# USB_Serial.net
KiCad netlist of a schematic drawn in Altium Designer
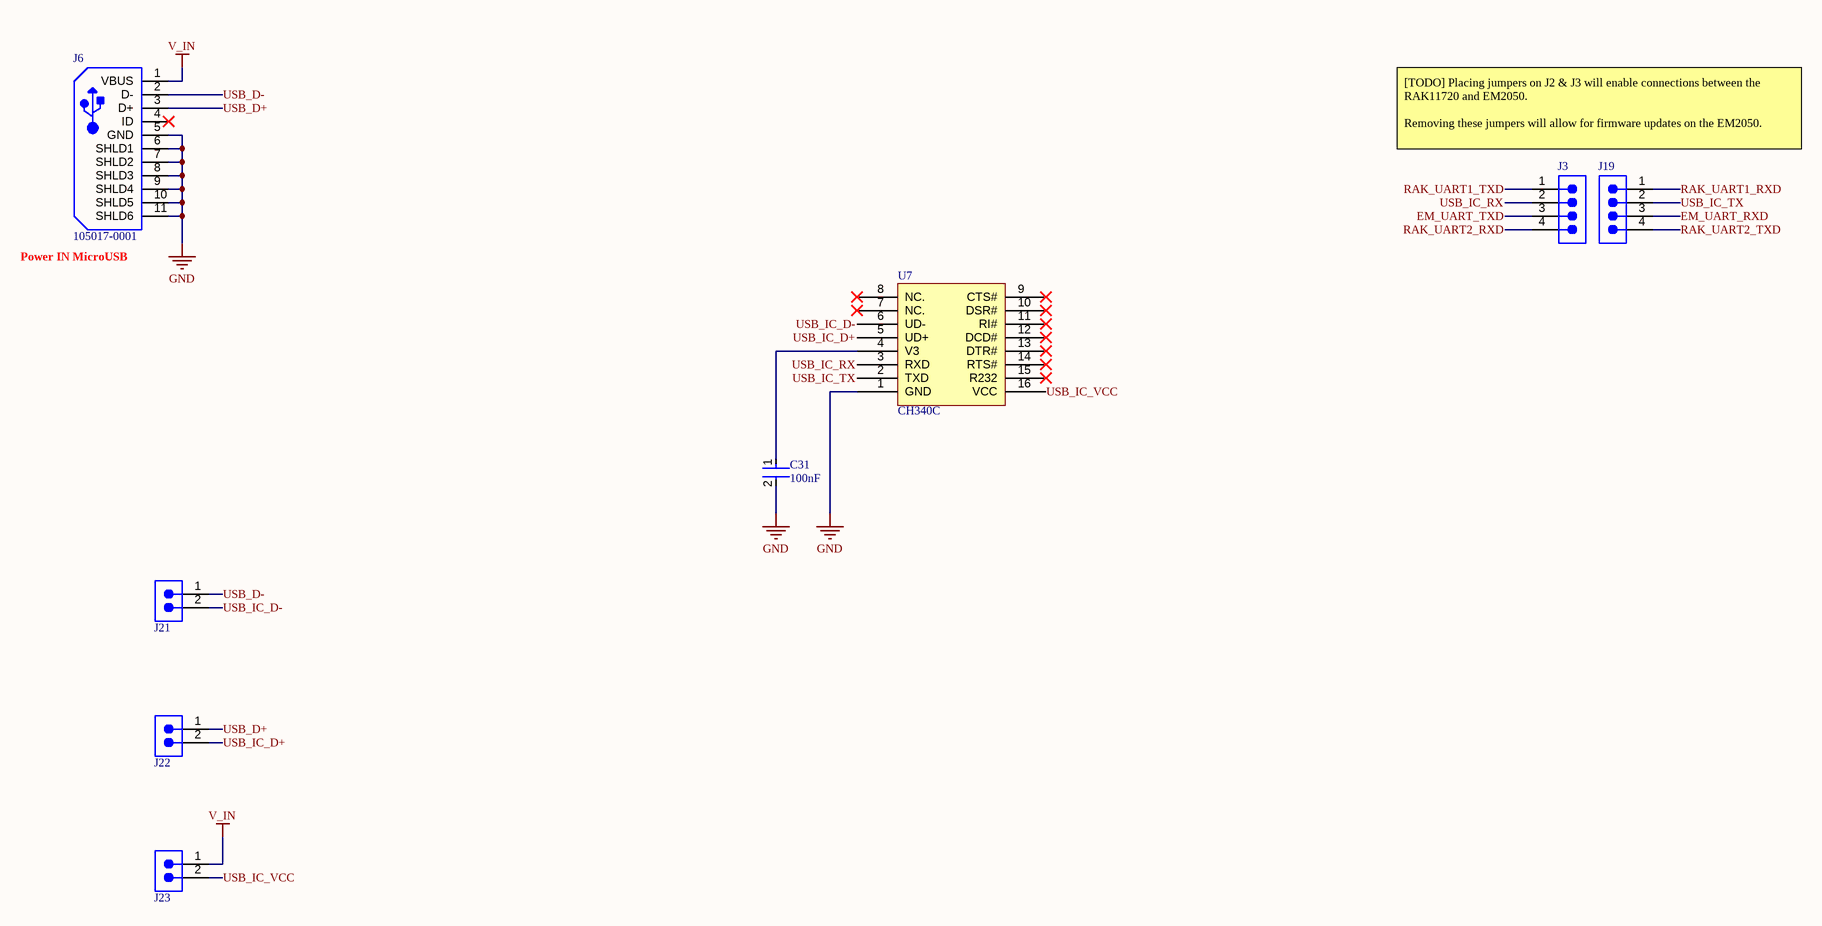
[diagram p0: USB_Serial.SchDoc]

(export (version "E")
  (design (tool "Eeschema 10.0.6"))
  (components
    (comp (ref "C31")
      (value "0402ZD104KAT2A")
      (footprint "FP-0402-L_1_0_1-W_0_5_0_1-IPC_C")
      (description "General Purpose Ceramic Capacitor, 0402, 100nF, 10%, X5R, 15%, 10V")
      (fields
        (field (name "VOLTAGE") "10V")
        (field (name "TOLERANCE") "10%")
        (field (name "CAPACITANCE") "100nF")
      )
      (libsource (lib "ApolloEcho_Dev_Kit") (part "b4654b650e69147ec39a6b967a45e02"))
    )
    (comp (ref "J3")
      (value "61300411121")
      (footprint "61300411121")
      (libsource (lib "ApolloEcho_Dev_Kit") (part "Header_Male_1R_04P"))
    )
    (comp (ref "J6")
      (value "105017-0001")
      (footprint "USB-MICRO-B_V")
      (fields (field (name "MANUFACTURER") "Molex"))
      (libsource (lib "ApolloEcho_Dev_Kit") (part "USB-5-6SHLD"))
    )
    (comp (ref "J19")
      (value "61300411121")
      (footprint "61300411121")
      (libsource (lib "ApolloEcho_Dev_Kit") (part "Header_Male_1R_04P"))
    )
    (comp (ref "J21")
      (value "61300211121")
      (footprint "61300211121")
      (libsource (lib "ApolloEcho_Dev_Kit") (part "Header_Male_1R_02P"))
    )
    (comp (ref "J22")
      (value "61300211121")
      (footprint "61300211121")
      (libsource (lib "ApolloEcho_Dev_Kit") (part "Header_Male_1R_02P"))
    )
    (comp (ref "J23")
      (value "61300211121")
      (footprint "61300211121")
      (libsource (lib "ApolloEcho_Dev_Kit") (part "Header_Male_1R_02P"))
    )
    (comp (ref "U7")
      (value "CH340C")
      (footprint "CH340C")
      (description "USB to Serial CH340 IC")
      (libsource (lib "ApolloEcho_Dev_Kit") (part "CH340C"))
    )
  )
  (nets
    (net (code "1") (name "/EM_UART_RXD") (class "Default")
      (node (ref "J19") (pin "3") (pinfunction "3_3") (pintype "passive"))
    )
    (net (code "2") (name "/EM_UART_TXD") (class "Default")
      (node (ref "J3") (pin "3") (pinfunction "3_3") (pintype "passive"))
    )
    (net (code "3") (name "/RAK_UART1_RXD") (class "Default")
      (node (ref "J19") (pin "1") (pinfunction "1_1") (pintype "passive"))
    )
    (net (code "4") (name "/RAK_UART1_TXD") (class "Default")
      (node (ref "J3") (pin "1") (pinfunction "1_1") (pintype "passive"))
    )
    (net (code "5") (name "/RAK_UART2_RXD") (class "Default")
      (node (ref "J3") (pin "4") (pinfunction "4_4") (pintype "passive"))
    )
    (net (code "6") (name "/RAK_UART2_TXD") (class "Default")
      (node (ref "J19") (pin "4") (pinfunction "4_4") (pintype "passive"))
    )
    (net (code "7") (name "/USB_D+") (class "Default")
      (node (ref "J22") (pin "1") (pinfunction "1_1") (pintype "passive"))
      (node (ref "J6") (pin "3") (pinfunction "D+_3") (pintype "passive"))
    )
    (net (code "8") (name "/USB_D-") (class "Default")
      (node (ref "J21") (pin "1") (pinfunction "1_1") (pintype "passive"))
      (node (ref "J6") (pin "2") (pinfunction "D-_2") (pintype "passive"))
    )
    (net (code "9") (name "/USB_IC_D+") (class "Default")
      (node (ref "J22") (pin "2") (pinfunction "2_2") (pintype "passive"))
      (node (ref "U7") (pin "5") (pinfunction "UD+_5") (pintype "passive"))
    )
    (net (code "10") (name "/USB_IC_D-") (class "Default")
      (node (ref "J21") (pin "2") (pinfunction "2_2") (pintype "passive"))
      (node (ref "U7") (pin "6") (pinfunction "UD-_6") (pintype "passive"))
    )
    (net (code "11") (name "/USB_IC_RX") (class "Default")
      (node (ref "J3") (pin "2") (pinfunction "2_2") (pintype "passive"))
      (node (ref "U7") (pin "3") (pinfunction "RXD_3") (pintype "passive"))
    )
    (net (code "12") (name "/USB_IC_TX") (class "Default")
      (node (ref "J19") (pin "2") (pinfunction "2_2") (pintype "passive"))
      (node (ref "U7") (pin "2") (pinfunction "TXD_2") (pintype "passive"))
    )
    (net (code "13") (name "/USB_IC_VCC") (class "Default")
      (node (ref "J23") (pin "2") (pinfunction "2_2") (pintype "passive"))
      (node (ref "U7") (pin "16") (pinfunction "VCC_16") (pintype "passive"))
    )
    (net (code "14") (name "GND") (class "Default")
      (node (ref "C31") (pin "2") (pinfunction "2_2") (pintype "passive"))
      (node (ref "J6") (pin "10") (pinfunction "SHLD5_10") (pintype "passive"))
      (node (ref "J6") (pin "11") (pinfunction "SHLD6_11") (pintype "passive"))
      (node (ref "J6") (pin "5") (pinfunction "GND_5") (pintype "passive"))
      (node (ref "J6") (pin "6") (pinfunction "SHLD1_6") (pintype "passive"))
      (node (ref "J6") (pin "7") (pinfunction "SHLD2_7") (pintype "passive"))
      (node (ref "J6") (pin "8") (pinfunction "SHLD3_8") (pintype "passive"))
      (node (ref "J6") (pin "9") (pinfunction "SHLD4_9") (pintype "passive"))
      (node (ref "U7") (pin "1") (pinfunction "GND_1") (pintype "passive"))
    )
    (net (code "15") (name "Net-(U7-V3)") (class "Default")
      (node (ref "C31") (pin "1") (pinfunction "1_1") (pintype "passive"))
      (node (ref "U7") (pin "4") (pinfunction "V3_4") (pintype "passive"))
    )
    (net (code "16") (name "V_IN") (class "Default")
      (node (ref "J23") (pin "1") (pinfunction "1_1") (pintype "passive"))
      (node (ref "J6") (pin "1") (pinfunction "VBUS_1") (pintype "passive"))
    )
    (net (code "17") (name "unconnected-(J6-ID-Pad4)") (class "Default")
      (node (ref "J6") (pin "4") (pinfunction "ID_4") (pintype "passive+no_connect"))
    )
    (net (code "18") (name "unconnected-(U7-CTS#-Pad9)") (class "Default")
      (node (ref "U7") (pin "9") (pinfunction "CTS#_9") (pintype "passive+no_connect"))
    )
    (net (code "19") (name "unconnected-(U7-DCD#-Pad12)") (class "Default")
      (node (ref "U7") (pin "12") (pinfunction "DCD#_12") (pintype "passive+no_connect"))
    )
    (net (code "20") (name "unconnected-(U7-DSR#-Pad10)") (class "Default")
      (node (ref "U7") (pin "10") (pinfunction "DSR#_10") (pintype "passive+no_connect"))
    )
    (net (code "21") (name "unconnected-(U7-DTR#-Pad13)") (class "Default")
      (node (ref "U7") (pin "13") (pinfunction "DTR#_13") (pintype "passive+no_connect"))
    )
    (net (code "22") (name "unconnected-(U7-NC.-Pad7)") (class "Default")
      (node (ref "U7") (pin "7") (pinfunction "NC._7") (pintype "passive+no_connect"))
    )
    (net (code "23") (name "unconnected-(U7-NC.-Pad8)") (class "Default")
      (node (ref "U7") (pin "8") (pinfunction "NC._8") (pintype "passive+no_connect"))
    )
    (net (code "24") (name "unconnected-(U7-R232-Pad15)") (class "Default")
      (node (ref "U7") (pin "15") (pinfunction "R232_15") (pintype "passive+no_connect"))
    )
    (net (code "25") (name "unconnected-(U7-RI#-Pad11)") (class "Default")
      (node (ref "U7") (pin "11") (pinfunction "RI#_11") (pintype "passive+no_connect"))
    )
    (net (code "26") (name "unconnected-(U7-RTS#-Pad14)") (class "Default")
      (node (ref "U7") (pin "14") (pinfunction "RTS#_14") (pintype "passive+no_connect"))
    )
  )
)
